# board.net
KiCad netlist of a schematic drawn in EAGLE
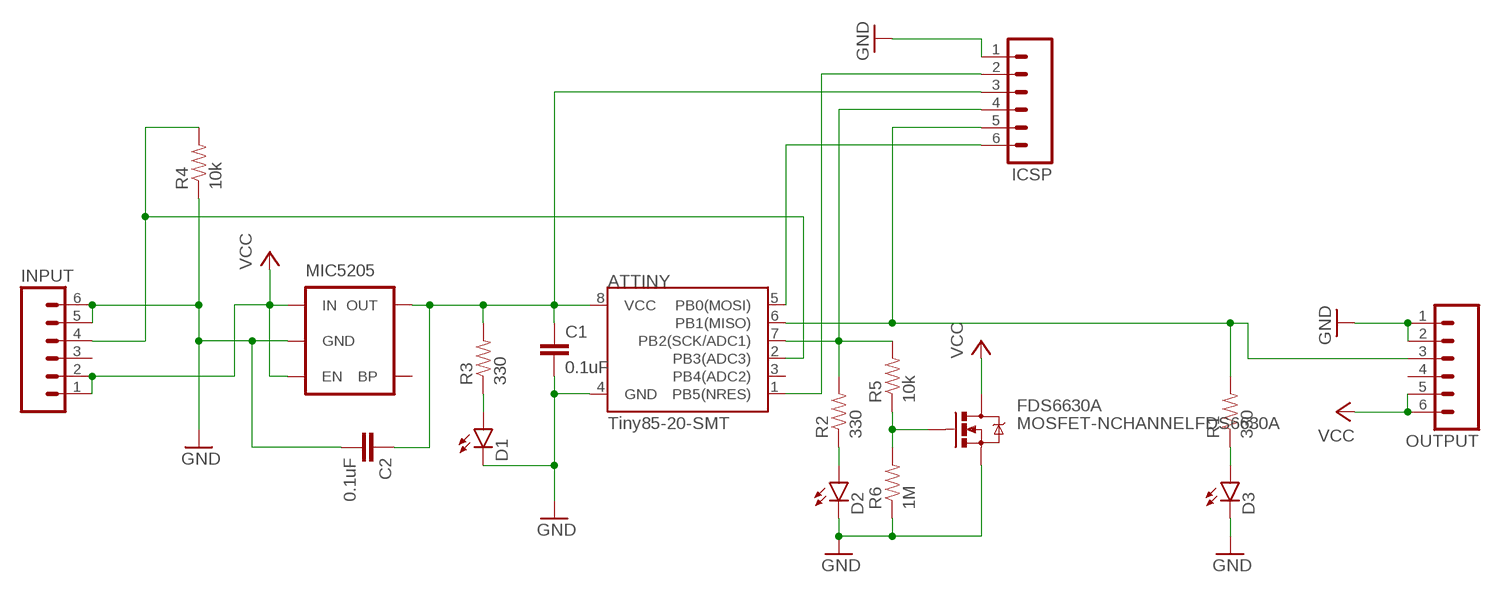
[diagram p0: schematic, sheet 1]

(export (version "E")
  (design (tool "Eeschema 10.0.6"))
  (components
    (comp (ref "ATTINY")
      (value "Tiny85-20-SMT")
      (footprint "eagle-import:SO08-EIAJ")
      (libsource (lib "eagle-import") (part "ATTINY45TINY85-20-SMT"))
    )
    (comp (ref "C1")
      (value "0.1uF")
      (footprint "eagle-import:0805")
      (libsource (lib "eagle-import") (part "1.0UF-25V-+80/-20(0805)"))
    )
    (comp (ref "C2")
      (value "0.1uF")
      (footprint "eagle-import:0805")
      (libsource (lib "eagle-import") (part "1.0UF-25V-+80/-20(0805)"))
    )
    (comp (ref "D1")
      (value "LED0603")
      (footprint "eagle-import:LED-0603")
      (libsource (lib "eagle-import") (part "LED0603"))
    )
    (comp (ref "D2")
      (value "LED0603")
      (footprint "eagle-import:LED-0603")
      (libsource (lib "eagle-import") (part "LED0603"))
    )
    (comp (ref "D3")
      (value "LED0603")
      (footprint "eagle-import:LED-0603")
      (libsource (lib "eagle-import") (part "LED0603"))
    )
    (comp (ref "FDS6630A")
      (value "MOSFET-NCHANNELFDS6630A")
      (footprint "eagle-import:SO08")
      (libsource (lib "eagle-import") (part "MOSFET-NCHANNELFDS6630A"))
    )
    (comp (ref "ICSP")
      (value "M06SMD-FEMALE-V2")
      (footprint "eagle-import:1X06-SMD-FEMALE-V2")
      (libsource (lib "eagle-import") (part "M06SMD-FEMALE-V2"))
    )
    (comp (ref "INPUT")
      (value "M06SMD-FEMALE-V2")
      (footprint "eagle-import:1X06-SMD-FEMALE-V2")
      (libsource (lib "eagle-import") (part "M06SMD-FEMALE-V2"))
    )
    (comp (ref "MIC5205")
      (value "MIC52055V")
      (footprint "eagle-import:SOT23-5")
      (libsource (lib "eagle-import") (part "MIC52055V"))
    )
    (comp (ref "OUTPUT")
      (value "M06SMD-FEMALE-V2")
      (footprint "eagle-import:1X06-SMD-FEMALE-V2")
      (libsource (lib "eagle-import") (part "M06SMD-FEMALE-V2"))
    )
    (comp (ref "R1")
      (value "330")
      (footprint "eagle-import:0603-RES")
      (libsource (lib "eagle-import") (part "RESISTOR0603"))
    )
    (comp (ref "R2")
      (value "330")
      (footprint "eagle-import:0603-RES")
      (libsource (lib "eagle-import") (part "RESISTOR0603"))
    )
    (comp (ref "R3")
      (value "330")
      (footprint "eagle-import:0603-RES")
      (libsource (lib "eagle-import") (part "RESISTOR0603"))
    )
    (comp (ref "R4")
      (value "10k")
      (footprint "eagle-import:0603-RES")
      (libsource (lib "eagle-import") (part "RESISTOR0603"))
    )
    (comp (ref "R5")
      (value "10k")
      (footprint "eagle-import:0805")
      (libsource (lib "eagle-import") (part "RESISTOR0805-RES"))
    )
    (comp (ref "R6")
      (value "1M")
      (footprint "eagle-import:0805")
      (libsource (lib "eagle-import") (part "RESISTOR0805-RES"))
    )
  )
  (nets
    (net (code "1") (name "GND") (class "Default")
      (node (ref "ATTINY") (pin "4") (pinfunction "GND_4") (pintype "bidirectional"))
      (node (ref "C1") (pin "2") (pinfunction "2_2") (pintype "passive"))
      (node (ref "C2") (pin "2") (pinfunction "2_2") (pintype "passive"))
      (node (ref "D1") (pin "C") (pinfunction "C_C") (pintype "passive"))
      (node (ref "D2") (pin "C") (pinfunction "C_C") (pintype "passive"))
      (node (ref "D3") (pin "C") (pinfunction "C_C") (pintype "passive"))
      (node (ref "FDS6630A") (pin "1") (pinfunction "S_1") (pintype "passive"))
      (node (ref "FDS6630A") (pin "2") (pinfunction "S_2") (pintype "passive"))
      (node (ref "FDS6630A") (pin "3") (pinfunction "S_3") (pintype "passive"))
      (node (ref "ICSP") (pin "1") (pinfunction "1_1") (pintype "passive"))
      (node (ref "INPUT") (pin "5") (pinfunction "5_5") (pintype "passive"))
      (node (ref "INPUT") (pin "6") (pinfunction "6_6") (pintype "passive"))
      (node (ref "MIC5205") (pin "2") (pinfunction "GND_2") (pintype "input"))
      (node (ref "OUTPUT") (pin "1") (pinfunction "1_1") (pintype "passive"))
      (node (ref "OUTPUT") (pin "2") (pinfunction "2_2") (pintype "passive"))
      (node (ref "R4") (pin "1") (pinfunction "1_1") (pintype "passive"))
      (node (ref "R6") (pin "1") (pinfunction "1_1") (pintype "passive"))
    )
    (net (code "2") (name "Net-(ATTINY-PB0(MOSI))") (class "Default")
      (node (ref "ATTINY") (pin "5") (pinfunction "PB0(MOSI)_5") (pintype "bidirectional"))
      (node (ref "ICSP") (pin "6") (pinfunction "6_6") (pintype "passive"))
    )
    (net (code "3") (name "Net-(ATTINY-PB1(MISO))") (class "Default")
      (node (ref "ATTINY") (pin "6") (pinfunction "PB1(MISO)_6") (pintype "bidirectional"))
      (node (ref "ICSP") (pin "5") (pinfunction "5_5") (pintype "passive"))
      (node (ref "OUTPUT") (pin "3") (pinfunction "3_3") (pintype "passive"))
      (node (ref "R1") (pin "2") (pinfunction "2_2") (pintype "passive"))
    )
    (net (code "4") (name "Net-(ATTINY-PB2(SCK{slash}ADC1))") (class "Default")
      (node (ref "ATTINY") (pin "7") (pinfunction "PB2(SCK/ADC1)_7") (pintype "bidirectional"))
      (node (ref "ICSP") (pin "4") (pinfunction "4_4") (pintype "passive"))
      (node (ref "R2") (pin "2") (pinfunction "2_2") (pintype "passive"))
      (node (ref "R5") (pin "2") (pinfunction "2_2") (pintype "passive"))
    )
    (net (code "5") (name "Net-(ATTINY-PB3(ADC3))") (class "Default")
      (node (ref "ATTINY") (pin "2") (pinfunction "PB3(ADC3)_2") (pintype "bidirectional"))
      (node (ref "INPUT") (pin "4") (pinfunction "4_4") (pintype "passive"))
      (node (ref "R4") (pin "2") (pinfunction "2_2") (pintype "passive"))
    )
    (net (code "6") (name "Net-(ATTINY-PB5(NRES))") (class "Default")
      (node (ref "ATTINY") (pin "1") (pinfunction "PB5(NRES)_1") (pintype "bidirectional"))
      (node (ref "ICSP") (pin "2") (pinfunction "2_2") (pintype "passive"))
    )
    (net (code "7") (name "Net-(ATTINY-VCC)") (class "Default")
      (node (ref "ATTINY") (pin "8") (pinfunction "VCC_8") (pintype "bidirectional"))
      (node (ref "C1") (pin "1") (pinfunction "1_1") (pintype "passive"))
      (node (ref "C2") (pin "1") (pinfunction "1_1") (pintype "passive"))
      (node (ref "ICSP") (pin "3") (pinfunction "3_3") (pintype "passive"))
      (node (ref "MIC5205") (pin "5") (pinfunction "OUT_5") (pintype "passive"))
      (node (ref "R3") (pin "2") (pinfunction "2_2") (pintype "passive"))
    )
    (net (code "8") (name "Net-(D1-PadA)") (class "Default")
      (node (ref "D1") (pin "A") (pinfunction "A_A") (pintype "passive"))
      (node (ref "R3") (pin "1") (pinfunction "1_1") (pintype "passive"))
    )
    (net (code "9") (name "Net-(D2-PadA)") (class "Default")
      (node (ref "D2") (pin "A") (pinfunction "A_A") (pintype "passive"))
      (node (ref "R2") (pin "1") (pinfunction "1_1") (pintype "passive"))
    )
    (net (code "10") (name "Net-(D3-PadA)") (class "Default")
      (node (ref "D3") (pin "A") (pinfunction "A_A") (pintype "passive"))
      (node (ref "R1") (pin "1") (pinfunction "1_1") (pintype "passive"))
    )
    (net (code "11") (name "Net-(FDS6630A-G)") (class "Default")
      (node (ref "FDS6630A") (pin "4") (pinfunction "G_4") (pintype "passive"))
      (node (ref "R5") (pin "1") (pinfunction "1_1") (pintype "passive"))
      (node (ref "R6") (pin "2") (pinfunction "2_2") (pintype "passive"))
    )
    (net (code "12") (name "VCC") (class "Default")
      (node (ref "FDS6630A") (pin "5") (pinfunction "D_5") (pintype "passive"))
      (node (ref "FDS6630A") (pin "6") (pinfunction "D_6") (pintype "passive"))
      (node (ref "FDS6630A") (pin "7") (pinfunction "D_7") (pintype "passive"))
      (node (ref "FDS6630A") (pin "8") (pinfunction "D_8") (pintype "passive"))
      (node (ref "INPUT") (pin "1") (pinfunction "1_1") (pintype "passive"))
      (node (ref "INPUT") (pin "2") (pinfunction "2_2") (pintype "passive"))
      (node (ref "MIC5205") (pin "1") (pinfunction "IN_1") (pintype "input"))
      (node (ref "MIC5205") (pin "3") (pinfunction "EN_3") (pintype "input"))
      (node (ref "OUTPUT") (pin "5") (pinfunction "5_5") (pintype "passive"))
      (node (ref "OUTPUT") (pin "6") (pinfunction "6_6") (pintype "passive"))
    )
    (net (code "13") (name "unconnected-(ATTINY-PB4(ADC2)-Pad3)") (class "Default")
      (node (ref "ATTINY") (pin "3") (pinfunction "PB4(ADC2)_3") (pintype "bidirectional"))
    )
    (net (code "14") (name "unconnected-(INPUT-Pad3)") (class "Default")
      (node (ref "INPUT") (pin "3") (pinfunction "3_3") (pintype "passive"))
    )
    (net (code "15") (name "unconnected-(MIC5205-BP-Pad4)") (class "Default")
      (node (ref "MIC5205") (pin "4") (pinfunction "BP_4") (pintype "input"))
    )
    (net (code "16") (name "unconnected-(OUTPUT-Pad4)") (class "Default")
      (node (ref "OUTPUT") (pin "4") (pinfunction "4_4") (pintype "passive"))
    )
  )
)
